# DSP_Board_Headers.net
KiCad netlist of a schematic drawn in Altium Designer
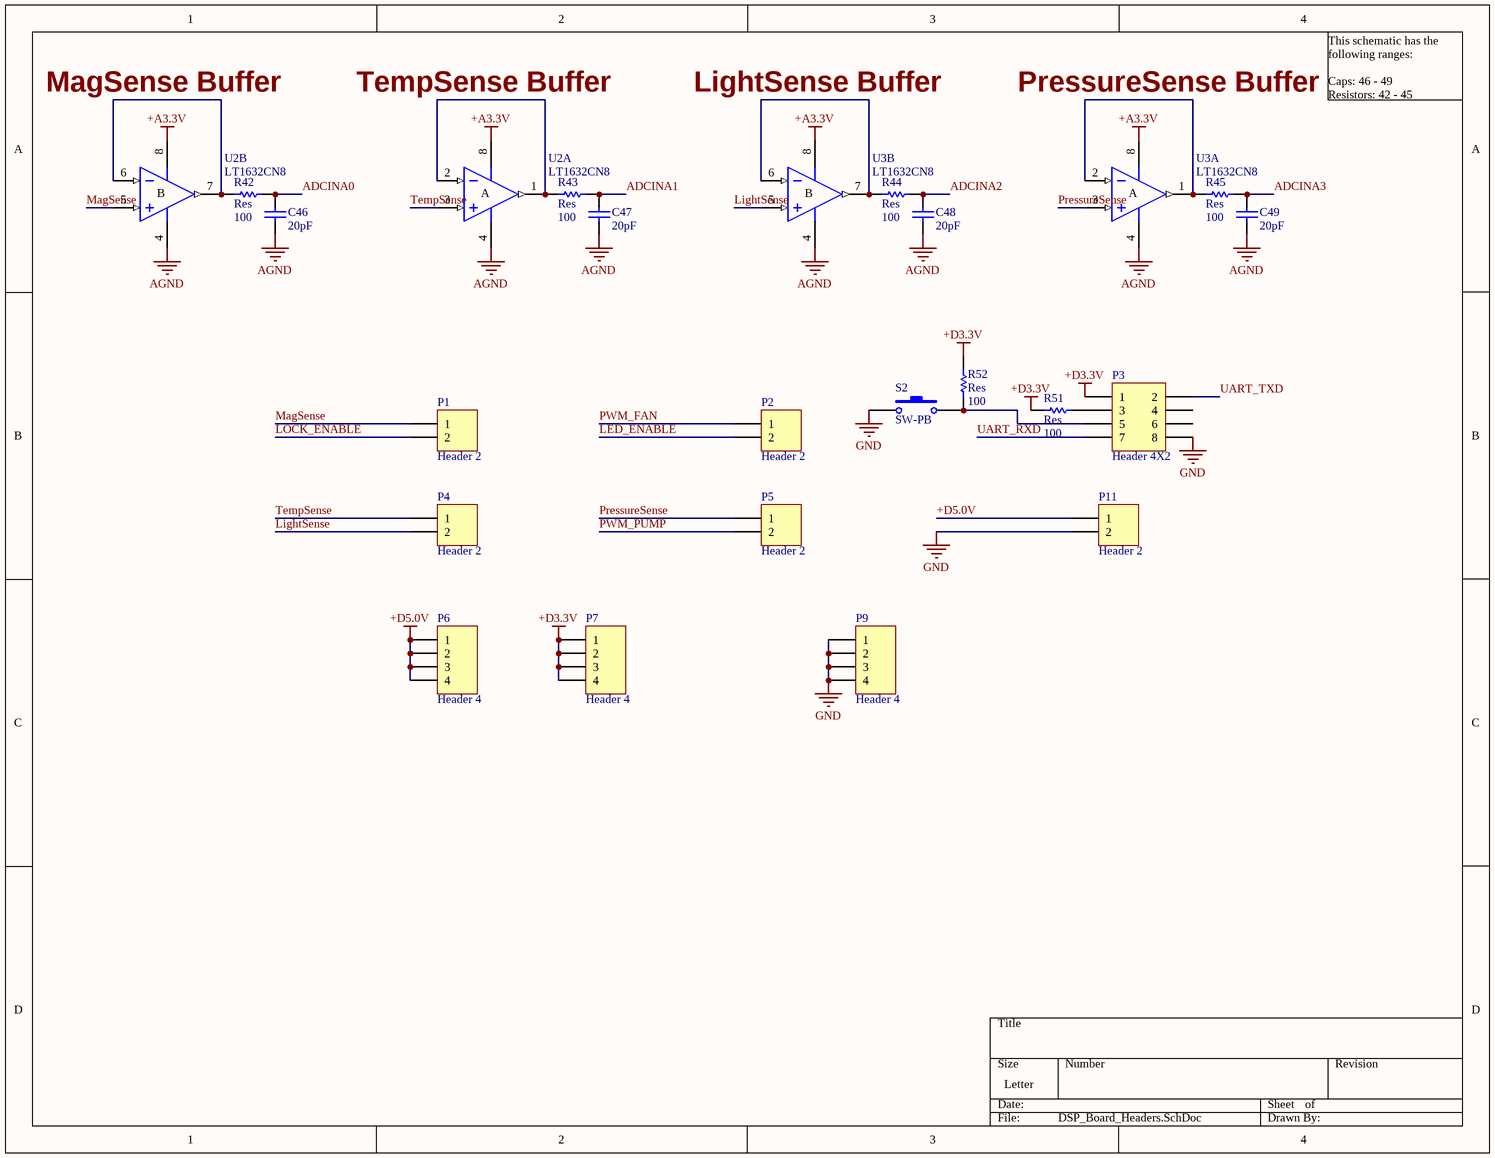
[diagram p0: DSP_Board_Headers.SchDoc]

(export (version "E")
  (design (tool "Eeschema 10.0.6"))
  (components
    (comp (ref "C46")
      (value "20pF")
      (footprint "0805")
      (description "Capacitor (Semiconductor SIM Model)")
      (fields (field (name "Comment") "Cap Semi") (field (name "PUBLISHER") "Altium Limited"))
      (libsource (lib "TMS320F28335GF") (part "Cap Semi"))
    )
    (comp (ref "C47")
      (value "20pF")
      (footprint "0805")
      (description "Capacitor (Semiconductor SIM Model)")
      (fields (field (name "Comment") "Cap Semi") (field (name "PUBLISHER") "Altium Limited"))
      (libsource (lib "TMS320F28335GF") (part "Cap Semi"))
    )
    (comp (ref "C48")
      (value "20pF")
      (footprint "0805")
      (description "Capacitor (Semiconductor SIM Model)")
      (fields (field (name "Comment") "Cap Semi") (field (name "PUBLISHER") "Altium Limited"))
      (libsource (lib "TMS320F28335GF") (part "Cap Semi"))
    )
    (comp (ref "C49")
      (value "20pF")
      (footprint "0805")
      (description "Capacitor (Semiconductor SIM Model)")
      (fields (field (name "Comment") "Cap Semi") (field (name "PUBLISHER") "Altium Limited"))
      (libsource (lib "TMS320F28335GF") (part "Cap Semi"))
    )
    (comp (ref "P1")
      (value "Header 2")
      (footprint "HDR1X2")
      (description "Header, 2-Pin")
      (fields (field (name "PUBLISHER") "Altium Limited"))
      (libsource (lib "Miscellaneous Connectors") (part "Header 2"))
    )
    (comp (ref "P2")
      (value "Header 2")
      (footprint "HDR1X2")
      (description "Header, 2-Pin")
      (fields (field (name "PUBLISHER") "Altium Limited"))
      (libsource (lib "Miscellaneous Connectors") (part "Header 2"))
    )
    (comp (ref "P3")
      (value "Header 4X2")
      (footprint "HDR2X4")
      (description "Header, 4-Pin, Dual row")
      (fields (field (name "PUBLISHER") "Altium Limited"))
      (libsource (lib "Miscellaneous Connectors") (part "Header 4X2"))
    )
    (comp (ref "P4")
      (value "Header 2")
      (footprint "HDR1X2")
      (description "Header, 2-Pin")
      (fields (field (name "PUBLISHER") "Altium Limited"))
      (libsource (lib "Miscellaneous Connectors") (part "Header 2"))
    )
    (comp (ref "P5")
      (value "Header 2")
      (footprint "HDR1X2")
      (description "Header, 2-Pin")
      (fields (field (name "PUBLISHER") "Altium Limited"))
      (libsource (lib "Miscellaneous Connectors") (part "Header 2"))
    )
    (comp (ref "P6")
      (value "Header 4")
      (footprint "HDR1X4")
      (description "Header, 4-Pin")
      (fields (field (name "PUBLISHER") "Altium Limited"))
      (libsource (lib "Miscellaneous Connectors") (part "Header 4"))
    )
    (comp (ref "P7")
      (value "Header 4")
      (footprint "HDR1X4")
      (description "Header, 4-Pin")
      (fields (field (name "PUBLISHER") "Altium Limited"))
      (libsource (lib "Miscellaneous Connectors") (part "Header 4"))
    )
    (comp (ref "P9")
      (value "Header 4")
      (footprint "HDR1X4")
      (description "Header, 4-Pin")
      (fields (field (name "PUBLISHER") "Altium Limited"))
      (libsource (lib "Miscellaneous Connectors") (part "Header 4"))
    )
    (comp (ref "P11")
      (value "Header 2")
      (footprint "HDR1X2")
      (description "Header, 2-Pin")
      (fields (field (name "PUBLISHER") "Altium Limited"))
      (libsource (lib "Miscellaneous Connectors") (part "Header 2"))
    )
    (comp (ref "R42")
      (value "Res")
      (footprint "0805")
      (description "Semiconductor Resistor")
      (fields (field (name "ALTIUM_VALUE") "100") (field (name "PUBLISHER") "Altium Limited"))
      (libsource (lib "TMS320F28335GF") (part "Res Semi"))
    )
    (comp (ref "R43")
      (value "Res")
      (footprint "0805")
      (description "Semiconductor Resistor")
      (fields (field (name "ALTIUM_VALUE") "100") (field (name "PUBLISHER") "Altium Limited"))
      (libsource (lib "TMS320F28335GF") (part "Res Semi"))
    )
    (comp (ref "R44")
      (value "Res")
      (footprint "0805")
      (description "Semiconductor Resistor")
      (fields (field (name "ALTIUM_VALUE") "100") (field (name "PUBLISHER") "Altium Limited"))
      (libsource (lib "TMS320F28335GF") (part "Res Semi"))
    )
    (comp (ref "R45")
      (value "Res")
      (footprint "0805")
      (description "Semiconductor Resistor")
      (fields (field (name "ALTIUM_VALUE") "100") (field (name "PUBLISHER") "Altium Limited"))
      (libsource (lib "TMS320F28335GF") (part "Res Semi"))
    )
    (comp (ref "R51")
      (value "Res")
      (footprint "0805")
      (description "Semiconductor Resistor")
      (fields (field (name "ALTIUM_VALUE") "100") (field (name "PUBLISHER") "Altium Limited"))
      (libsource (lib "TMS320F28335GF") (part "Res Semi"))
    )
    (comp (ref "R52")
      (value "Res")
      (footprint "0805")
      (description "Semiconductor Resistor")
      (fields (field (name "ALTIUM_VALUE") "100") (field (name "PUBLISHER") "Altium Limited"))
      (libsource (lib "TMS320F28335GF") (part "Res Semi"))
    )
    (comp (ref "S2")
      (value "SW-PB")
      (footprint "SW PB")
      (description "DIGIKEY SW400-ND")
      (fields (field (name "PUBLISHER") "Altium Limited"))
      (libsource (lib "ECE LIB new") (part "SW-PB_2"))
    )
    (comp (ref "U2")
      (value "LT1632CN8")
      (footprint "DIP-8")
      (description "45MHz, 45V/µs, Dual Rail-to-Rail Input and Output Precision Operational Amplifier")
      (fields (field (name "PUBLISHER") "Altium Limited"))
      (libsource (lib "ECE LIB new") (part "LT1632CN8"))
    )
    (comp (ref "U3")
      (value "LT1632CN8")
      (footprint "SO08")
      (description "45MHz, 45V/µs, Dual Rail-to-Rail Input and Output Precision Operational Amplifier")
      (fields (field (name "PUBLISHER") "Altium Limited"))
      (libsource (lib "ECE LIB new") (part "LT1632CN8"))
    )
  )
  (nets
    (net (code "1") (name "+A3.3V") (class "Default")
      (node (ref "U2") (pin "8") (pinfunction "V+_8") (pintype "power_in"))
      (node (ref "U3") (pin "8") (pinfunction "V+_8") (pintype "power_in"))
    )
    (net (code "2") (name "+D3.3V") (class "Default")
      (node (ref "P3") (pin "1") (pinfunction "1_1") (pintype "passive"))
      (node (ref "P7") (pin "1") (pinfunction "1_1") (pintype "passive"))
      (node (ref "P7") (pin "2") (pinfunction "2_2") (pintype "passive"))
      (node (ref "P7") (pin "3") (pinfunction "3_3") (pintype "passive"))
      (node (ref "P7") (pin "4") (pinfunction "4_4") (pintype "passive"))
      (node (ref "R51") (pin "1") (pinfunction "1_1") (pintype "passive"))
      (node (ref "R52") (pin "2") (pinfunction "2_2") (pintype "passive"))
    )
    (net (code "3") (name "+D5.0V") (class "Default")
      (node (ref "P11") (pin "1") (pinfunction "1_1") (pintype "passive"))
      (node (ref "P6") (pin "1") (pinfunction "1_1") (pintype "passive"))
      (node (ref "P6") (pin "2") (pinfunction "2_2") (pintype "passive"))
      (node (ref "P6") (pin "3") (pinfunction "3_3") (pintype "passive"))
      (node (ref "P6") (pin "4") (pinfunction "4_4") (pintype "passive"))
    )
    (net (code "4") (name "/ADCINA0") (class "Default")
      (node (ref "C46") (pin "2") (pinfunction "2_2") (pintype "passive"))
      (node (ref "R42") (pin "2") (pinfunction "2_2") (pintype "passive"))
    )
    (net (code "5") (name "/ADCINA1") (class "Default")
      (node (ref "C47") (pin "2") (pinfunction "2_2") (pintype "passive"))
      (node (ref "R43") (pin "2") (pinfunction "2_2") (pintype "passive"))
    )
    (net (code "6") (name "/ADCINA2") (class "Default")
      (node (ref "C48") (pin "2") (pinfunction "2_2") (pintype "passive"))
      (node (ref "R44") (pin "2") (pinfunction "2_2") (pintype "passive"))
    )
    (net (code "7") (name "/ADCINA3") (class "Default")
      (node (ref "C49") (pin "2") (pinfunction "2_2") (pintype "passive"))
      (node (ref "R45") (pin "2") (pinfunction "2_2") (pintype "passive"))
    )
    (net (code "8") (name "/LED_ENABLE") (class "Default")
      (node (ref "P2") (pin "2") (pinfunction "2_2") (pintype "passive"))
    )
    (net (code "9") (name "/LOCK_ENABLE") (class "Default")
      (node (ref "P1") (pin "2") (pinfunction "2_2") (pintype "passive"))
    )
    (net (code "10") (name "/LightSense") (class "Default")
      (node (ref "P4") (pin "2") (pinfunction "2_2") (pintype "passive"))
      (node (ref "U3") (pin "5") (pinfunction "IN+_5") (pintype "input"))
    )
    (net (code "11") (name "/MagSense") (class "Default")
      (node (ref "P1") (pin "1") (pinfunction "1_1") (pintype "passive"))
      (node (ref "U2") (pin "5") (pinfunction "IN+_5") (pintype "input"))
    )
    (net (code "12") (name "/PWM_FAN") (class "Default")
      (node (ref "P2") (pin "1") (pinfunction "1_1") (pintype "passive"))
    )
    (net (code "13") (name "/PWM_PUMP") (class "Default")
      (node (ref "P5") (pin "2") (pinfunction "2_2") (pintype "passive"))
    )
    (net (code "14") (name "/PressureSense") (class "Default")
      (node (ref "P5") (pin "1") (pinfunction "1_1") (pintype "passive"))
      (node (ref "U3") (pin "3") (pinfunction "IN+_3") (pintype "input"))
    )
    (net (code "15") (name "/TempSense") (class "Default")
      (node (ref "P4") (pin "1") (pinfunction "1_1") (pintype "passive"))
      (node (ref "U2") (pin "3") (pinfunction "IN+_3") (pintype "input"))
    )
    (net (code "16") (name "/UART_RXD") (class "Default")
      (node (ref "P3") (pin "7") (pinfunction "7_7") (pintype "passive"))
    )
    (net (code "17") (name "/UART_TXD") (class "Default")
      (node (ref "P3") (pin "2") (pinfunction "2_2") (pintype "passive"))
    )
    (net (code "18") (name "AGND") (class "Default")
      (node (ref "C46") (pin "1") (pinfunction "1_1") (pintype "passive"))
      (node (ref "C47") (pin "1") (pinfunction "1_1") (pintype "passive"))
      (node (ref "C48") (pin "1") (pinfunction "1_1") (pintype "passive"))
      (node (ref "C49") (pin "1") (pinfunction "1_1") (pintype "passive"))
      (node (ref "U2") (pin "4") (pinfunction "V-_4") (pintype "power_in"))
      (node (ref "U3") (pin "4") (pinfunction "V-_4") (pintype "power_in"))
    )
    (net (code "19") (name "GND") (class "Default")
      (node (ref "P11") (pin "2") (pinfunction "2_2") (pintype "passive"))
      (node (ref "P3") (pin "8") (pinfunction "8_8") (pintype "passive"))
      (node (ref "P9") (pin "1") (pinfunction "1_1") (pintype "passive"))
      (node (ref "P9") (pin "2") (pinfunction "2_2") (pintype "passive"))
      (node (ref "P9") (pin "3") (pinfunction "3_3") (pintype "passive"))
      (node (ref "P9") (pin "4") (pinfunction "4_4") (pintype "passive"))
      (node (ref "S2") (pin "1") (pinfunction "1_1") (pintype "passive"))
    )
    (net (code "20") (name "Net-(P3-Pad3)") (class "Default")
      (node (ref "P3") (pin "3") (pinfunction "3_3") (pintype "passive"))
      (node (ref "R51") (pin "2") (pinfunction "2_2") (pintype "passive"))
    )
    (net (code "21") (name "Net-(P3-Pad5)") (class "Default")
      (node (ref "P3") (pin "5") (pinfunction "5_5") (pintype "passive"))
      (node (ref "R52") (pin "1") (pinfunction "1_1") (pintype "passive"))
      (node (ref "S2") (pin "2") (pinfunction "2_2") (pintype "passive"))
    )
    (net (code "22") (name "Net-(U2A-IN-)") (class "Default")
      (node (ref "R43") (pin "1") (pinfunction "1_1") (pintype "passive"))
      (node (ref "U2") (pin "1") (pinfunction "OUT_1") (pintype "output"))
      (node (ref "U2") (pin "2") (pinfunction "IN-_2") (pintype "input"))
    )
    (net (code "23") (name "Net-(U2B-IN-)") (class "Default")
      (node (ref "R42") (pin "1") (pinfunction "1_1") (pintype "passive"))
      (node (ref "U2") (pin "6") (pinfunction "IN-_6") (pintype "input"))
      (node (ref "U2") (pin "7") (pinfunction "OUT_7") (pintype "output"))
    )
    (net (code "24") (name "Net-(U3A-IN-)") (class "Default")
      (node (ref "R45") (pin "1") (pinfunction "1_1") (pintype "passive"))
      (node (ref "U3") (pin "1") (pinfunction "OUT_1") (pintype "output"))
      (node (ref "U3") (pin "2") (pinfunction "IN-_2") (pintype "input"))
    )
    (net (code "25") (name "Net-(U3B-IN-)") (class "Default")
      (node (ref "R44") (pin "1") (pinfunction "1_1") (pintype "passive"))
      (node (ref "U3") (pin "6") (pinfunction "IN-_6") (pintype "input"))
      (node (ref "U3") (pin "7") (pinfunction "OUT_7") (pintype "output"))
    )
    (net (code "26") (name "unconnected-(P3-Pad4)") (class "Default")
      (node (ref "P3") (pin "4") (pinfunction "4_4") (pintype "passive"))
    )
    (net (code "27") (name "unconnected-(P3-Pad6)") (class "Default")
      (node (ref "P3") (pin "6") (pinfunction "6_6") (pintype "passive"))
    )
  )
)
